# rtc.net
KiCad netlist of a schematic drawn in EAGLE
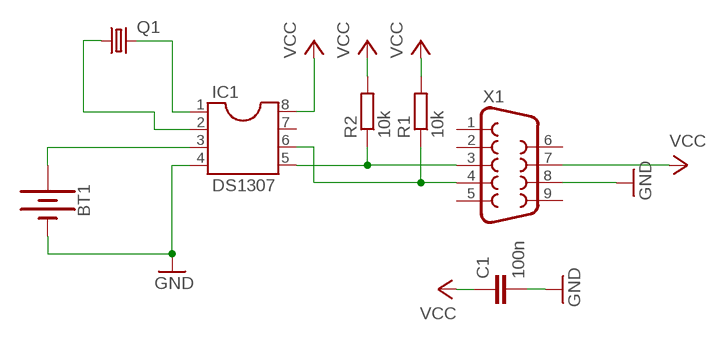
[diagram p0: schematic, sheet 1]

(export (version "E")
  (design (tool "Eeschema 10.0.6"))
  (components
    (comp (ref "BT1")
      (value "BATTERY-20MM_PTH")
      (footprint "eagle-import:BATTCOM_20MM_PTH")
      (libsource (lib "eagle-import") (part "BATTERY-20MM_PTH"))
    )
    (comp (ref "C1")
      (value "100n")
      (footprint "eagle-import:C025-025X050")
      (libsource (lib "eagle-import") (part "C-EU025-025X050"))
    )
    (comp (ref "IC1")
      (value "DS1307")
      (footprint "eagle-import:DIL08")
      (libsource (lib "eagle-import") (part "DIL8"))
    )
    (comp (ref "Q1")
      (value "CRYSTALTC26V")
      (footprint "eagle-import:TC26V")
      (libsource (lib "eagle-import") (part "CRYSTALTC26V"))
    )
    (comp (ref "R1")
      (value "10k")
      (footprint "eagle-import:0204_7")
      (libsource (lib "eagle-import") (part "R-EU_0204/7"))
    )
    (comp (ref "R2")
      (value "10k")
      (footprint "eagle-import:0204_7")
      (libsource (lib "eagle-import") (part "R-EU_0204/7"))
    )
    (comp (ref "X1")
      (value "F09D")
      (footprint "eagle-import:F09D")
      (libsource (lib "eagle-import") (part "F09D"))
    )
  )
  (nets
    (net (code "1") (name "GND") (class "Default")
      (node (ref "BT1") (pin "2") (pinfunction "-_2") (pintype "power_in"))
      (node (ref "C1") (pin "2") (pinfunction "2_2") (pintype "passive"))
      (node (ref "IC1") (pin "4") (pinfunction "4_4") (pintype "passive"))
      (node (ref "X1") (pin "8") (pinfunction "8_8") (pintype "passive"))
    )
    (net (code "2") (name "Net-(BT1-+)") (class "Default")
      (node (ref "BT1") (pin "1") (pinfunction "+_1") (pintype "power_in"))
      (node (ref "IC1") (pin "3") (pinfunction "3_3") (pintype "passive"))
    )
    (net (code "3") (name "Net-(IC1-Pad1)") (class "Default")
      (node (ref "IC1") (pin "1") (pinfunction "1_1") (pintype "passive"))
      (node (ref "Q1") (pin "2") (pinfunction "2_2") (pintype "passive"))
    )
    (net (code "4") (name "Net-(IC1-Pad2)") (class "Default")
      (node (ref "IC1") (pin "2") (pinfunction "2_2") (pintype "passive"))
      (node (ref "Q1") (pin "1") (pinfunction "1_1") (pintype "passive"))
    )
    (net (code "5") (name "Net-(IC1-Pad5)") (class "Default")
      (node (ref "IC1") (pin "5") (pinfunction "5_5") (pintype "passive"))
      (node (ref "R2") (pin "1") (pinfunction "1_1") (pintype "passive"))
      (node (ref "X1") (pin "3") (pinfunction "3_3") (pintype "passive"))
    )
    (net (code "6") (name "Net-(IC1-Pad6)") (class "Default")
      (node (ref "IC1") (pin "6") (pinfunction "6_6") (pintype "passive"))
      (node (ref "R1") (pin "1") (pinfunction "1_1") (pintype "passive"))
      (node (ref "X1") (pin "4") (pinfunction "4_4") (pintype "passive"))
    )
    (net (code "7") (name "VCC") (class "Default")
      (node (ref "C1") (pin "1") (pinfunction "1_1") (pintype "passive"))
      (node (ref "IC1") (pin "8") (pinfunction "8_8") (pintype "passive"))
      (node (ref "R1") (pin "2") (pinfunction "2_2") (pintype "passive"))
      (node (ref "R2") (pin "2") (pinfunction "2_2") (pintype "passive"))
      (node (ref "X1") (pin "7") (pinfunction "7_7") (pintype "passive"))
    )
    (net (code "8") (name "unconnected-(IC1-Pad7)") (class "Default")
      (node (ref "IC1") (pin "7") (pinfunction "7_7") (pintype "passive"))
    )
    (net (code "9") (name "unconnected-(X1-Pad1)") (class "Default")
      (node (ref "X1") (pin "1") (pinfunction "1_1") (pintype "passive"))
    )
    (net (code "10") (name "unconnected-(X1-Pad2)") (class "Default")
      (node (ref "X1") (pin "2") (pinfunction "2_2") (pintype "passive"))
    )
    (net (code "11") (name "unconnected-(X1-Pad5)") (class "Default")
      (node (ref "X1") (pin "5") (pinfunction "5_5") (pintype "passive"))
    )
    (net (code "12") (name "unconnected-(X1-Pad6)") (class "Default")
      (node (ref "X1") (pin "6") (pinfunction "6_6") (pintype "passive"))
    )
    (net (code "13") (name "unconnected-(X1-Pad9)") (class "Default")
      (node (ref "X1") (pin "9") (pinfunction "9_9") (pintype "passive"))
    )
  )
)
